# childA.net
KiCad netlist of a schematic drawn in Altium Designer
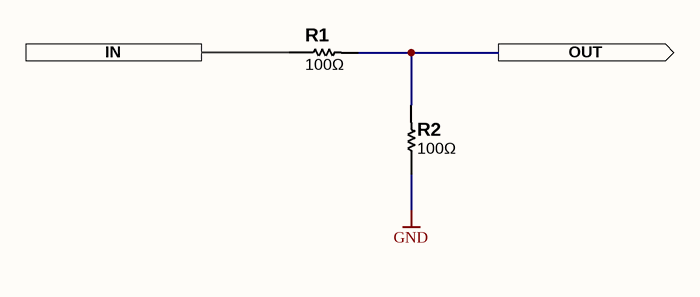
[diagram p0: childA.SchDoc]

(export (version "E")
  (design (tool "Eeschema 10.0.6"))
  (components
    (comp (ref "R1")
      (value "100Ω")
      (footprint "R0603_0.55MM_HD")
      (description "RES 100 OHM 1/10W 1% 0603 SMD")
      (fields
        (field (name "TOLERANCE") "±1%")
        (field (name "MANUFACTURER") "Panasonic Electronic Components")
      )
      (libsource (lib "wavenumber") (part "R_2P"))
    )
    (comp (ref "R2")
      (value "100Ω")
      (footprint "R0603_0.55MM_HD")
      (description "RES 100 OHM 1/10W 1% 0603 SMD")
      (fields
        (field (name "TOLERANCE") "±1%")
        (field (name "MANUFACTURER") "Panasonic Electronic Components")
      )
      (libsource (lib "wavenumber") (part "R_2P"))
    )
  )
  (nets
    (net (code "1") (name "/IN") (class "Default")
      (node (ref "R1") (pin "1") (pinfunction "1_1") (pintype "passive"))
    )
    (net (code "2") (name "/OUT") (class "Default")
      (node (ref "R1") (pin "2") (pinfunction "2_2") (pintype "passive"))
      (node (ref "R2") (pin "2") (pinfunction "2_2") (pintype "passive"))
    )
    (net (code "3") (name "GND") (class "Default")
      (node (ref "R2") (pin "1") (pinfunction "1_1") (pintype "passive"))
    )
  )
)
